# Mini-Mixer.net
KiCad netlist of a schematic drawn in EAGLE
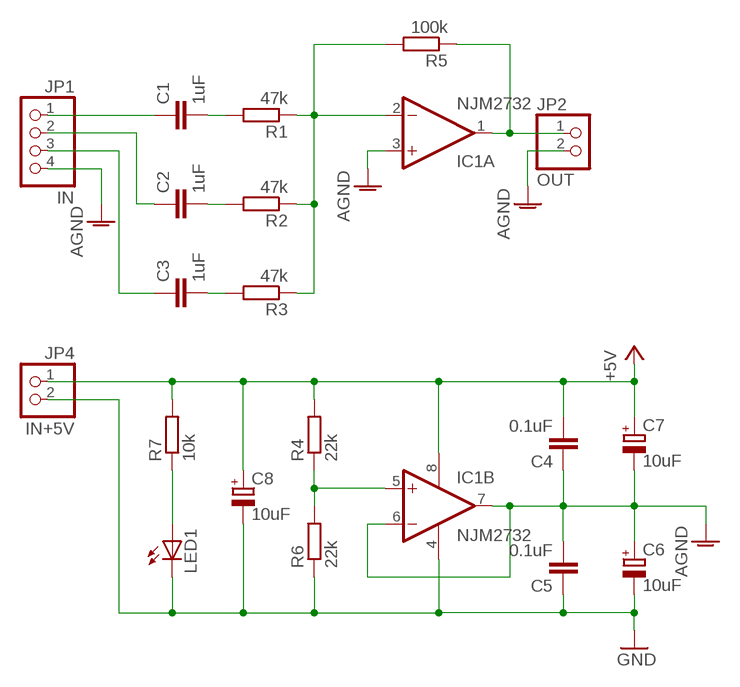
[diagram p0: schematic, sheet 1]

(export (version "E")
  (design (tool "Eeschema 10.0.6"))
  (components
    (comp (ref "C1")
      (value "1uF")
      (footprint "eagle-import:C050-050X075")
      (libsource (lib "eagle-import") (part "C-EU050-050X075"))
    )
    (comp (ref "C2")
      (value "1uF")
      (footprint "eagle-import:C050-050X075")
      (libsource (lib "eagle-import") (part "C-EU050-050X075"))
    )
    (comp (ref "C3")
      (value "1uF")
      (footprint "eagle-import:C050-050X075")
      (libsource (lib "eagle-import") (part "C-EU050-050X075"))
    )
    (comp (ref "C4")
      (value "0.1uF")
      (footprint "eagle-import:C025-024X044")
      (libsource (lib "eagle-import") (part "C-EU025-024X044"))
    )
    (comp (ref "C5")
      (value "0.1uF")
      (footprint "eagle-import:C025-024X044")
      (libsource (lib "eagle-import") (part "C-EU025-024X044"))
    )
    (comp (ref "C6")
      (value "10uF")
      (footprint "eagle-import:TT2D4L")
      (libsource (lib "eagle-import") (part "CPOL-EUTT2D4L"))
    )
    (comp (ref "C7")
      (value "10uF")
      (footprint "eagle-import:TT2D4L")
      (libsource (lib "eagle-import") (part "CPOL-EUTT2D4L"))
    )
    (comp (ref "C8")
      (value "10uF")
      (footprint "eagle-import:TT2D4L")
      (libsource (lib "eagle-import") (part "CPOL-EUTT2D4L"))
    )
    (comp (ref "IC1")
      (value "NJM2732")
      (footprint "eagle-import:DIL08")
      (libsource (lib "eagle-import") (part "4558NLM"))
    )
    (comp (ref "JP1")
      (value "IN")
      (footprint "eagle-import:1X04")
      (libsource (lib "eagle-import") (part "PINHD-1X4"))
    )
    (comp (ref "JP2")
      (value "OUT")
      (footprint "eagle-import:1X02")
      (libsource (lib "eagle-import") (part "PINHD-1X2"))
    )
    (comp (ref "JP4")
      (value "IN+5V")
      (footprint "eagle-import:1X02")
      (libsource (lib "eagle-import") (part "PINHD-1X2"))
    )
    (comp (ref "LED1")
      (value "LED3MM")
      (footprint "eagle-import:LED3MM")
      (libsource (lib "eagle-import") (part "LED3MM"))
    )
    (comp (ref "R1")
      (value "47k")
      (footprint "eagle-import:0207_7")
      (libsource (lib "eagle-import") (part "R-EU_0207/7"))
    )
    (comp (ref "R2")
      (value "47k")
      (footprint "eagle-import:0207_7")
      (libsource (lib "eagle-import") (part "R-EU_0207/7"))
    )
    (comp (ref "R3")
      (value "47k")
      (footprint "eagle-import:0207_7")
      (libsource (lib "eagle-import") (part "R-EU_0207/7"))
    )
    (comp (ref "R4")
      (value "22k")
      (footprint "eagle-import:0207_7")
      (libsource (lib "eagle-import") (part "R-EU_0207/7"))
    )
    (comp (ref "R5")
      (value "100k")
      (footprint "eagle-import:0207_7")
      (libsource (lib "eagle-import") (part "R-EU_0207/7"))
    )
    (comp (ref "R6")
      (value "22k")
      (footprint "eagle-import:0207_7")
      (libsource (lib "eagle-import") (part "R-EU_0207/7"))
    )
    (comp (ref "R7")
      (value "10k")
      (footprint "eagle-import:0207_7")
      (libsource (lib "eagle-import") (part "R-EU_0207/7"))
    )
  )
  (nets
    (net (code "1") (name "+5V") (class "Default")
      (node (ref "C4") (pin "2") (pinfunction "2_2") (pintype "passive"))
      (node (ref "C7") (pin "+") (pinfunction "+_+") (pintype "passive"))
      (node (ref "C8") (pin "+") (pinfunction "+_+") (pintype "passive"))
      (node (ref "IC1") (pin "8") (pinfunction "V+_8") (pintype "power_in"))
      (node (ref "JP4") (pin "1") (pinfunction "1_1") (pintype "passive"))
      (node (ref "R4") (pin "2") (pinfunction "2_2") (pintype "passive"))
      (node (ref "R7") (pin "2") (pinfunction "2_2") (pintype "passive"))
    )
    (net (code "2") (name "AGND") (class "Default")
      (node (ref "C4") (pin "1") (pinfunction "1_1") (pintype "passive"))
      (node (ref "C5") (pin "2") (pinfunction "2_2") (pintype "passive"))
      (node (ref "C6") (pin "+") (pinfunction "+_+") (pintype "passive"))
      (node (ref "C7") (pin "-") (pinfunction "-_-") (pintype "passive"))
      (node (ref "IC1") (pin "3") (pinfunction "+IN_3") (pintype "input"))
      (node (ref "IC1") (pin "6") (pinfunction "-IN_6") (pintype "input"))
      (node (ref "IC1") (pin "7") (pinfunction "OUT_7") (pintype "output"))
      (node (ref "JP1") (pin "4") (pinfunction "4_4") (pintype "passive"))
      (node (ref "JP2") (pin "2") (pinfunction "2_2") (pintype "passive"))
    )
    (net (code "3") (name "GND") (class "Default")
      (node (ref "C5") (pin "1") (pinfunction "1_1") (pintype "passive"))
      (node (ref "C6") (pin "-") (pinfunction "-_-") (pintype "passive"))
      (node (ref "C8") (pin "-") (pinfunction "-_-") (pintype "passive"))
      (node (ref "IC1") (pin "4") (pinfunction "V-_4") (pintype "power_in"))
      (node (ref "JP4") (pin "2") (pinfunction "2_2") (pintype "passive"))
      (node (ref "LED1") (pin "K") (pinfunction "C_K") (pintype "passive"))
      (node (ref "R6") (pin "1") (pinfunction "1_1") (pintype "passive"))
    )
    (net (code "4") (name "Net-(C1-Pad1)") (class "Default")
      (node (ref "C1") (pin "1") (pinfunction "1_1") (pintype "passive"))
      (node (ref "JP1") (pin "1") (pinfunction "1_1") (pintype "passive"))
    )
    (net (code "5") (name "Net-(C1-Pad2)") (class "Default")
      (node (ref "C1") (pin "2") (pinfunction "2_2") (pintype "passive"))
      (node (ref "R1") (pin "2") (pinfunction "2_2") (pintype "passive"))
    )
    (net (code "6") (name "Net-(C2-Pad1)") (class "Default")
      (node (ref "C2") (pin "1") (pinfunction "1_1") (pintype "passive"))
      (node (ref "JP1") (pin "2") (pinfunction "2_2") (pintype "passive"))
    )
    (net (code "7") (name "Net-(C2-Pad2)") (class "Default")
      (node (ref "C2") (pin "2") (pinfunction "2_2") (pintype "passive"))
      (node (ref "R2") (pin "2") (pinfunction "2_2") (pintype "passive"))
    )
    (net (code "8") (name "Net-(C3-Pad1)") (class "Default")
      (node (ref "C3") (pin "1") (pinfunction "1_1") (pintype "passive"))
      (node (ref "JP1") (pin "3") (pinfunction "3_3") (pintype "passive"))
    )
    (net (code "9") (name "Net-(C3-Pad2)") (class "Default")
      (node (ref "C3") (pin "2") (pinfunction "2_2") (pintype "passive"))
      (node (ref "R3") (pin "2") (pinfunction "2_2") (pintype "passive"))
    )
    (net (code "10") (name "Net-(IC1A--IN)") (class "Default")
      (node (ref "IC1") (pin "2") (pinfunction "-IN_2") (pintype "input"))
      (node (ref "R1") (pin "1") (pinfunction "1_1") (pintype "passive"))
      (node (ref "R2") (pin "1") (pinfunction "1_1") (pintype "passive"))
      (node (ref "R3") (pin "1") (pinfunction "1_1") (pintype "passive"))
      (node (ref "R5") (pin "2") (pinfunction "2_2") (pintype "passive"))
    )
    (net (code "11") (name "Net-(IC1A-OUT)") (class "Default")
      (node (ref "IC1") (pin "1") (pinfunction "OUT_1") (pintype "output"))
      (node (ref "JP2") (pin "1") (pinfunction "1_1") (pintype "passive"))
      (node (ref "R5") (pin "1") (pinfunction "1_1") (pintype "passive"))
    )
    (net (code "12") (name "Net-(IC1B-+IN)") (class "Default")
      (node (ref "IC1") (pin "5") (pinfunction "+IN_5") (pintype "input"))
      (node (ref "R4") (pin "1") (pinfunction "1_1") (pintype "passive"))
      (node (ref "R6") (pin "2") (pinfunction "2_2") (pintype "passive"))
    )
    (net (code "13") (name "Net-(LED1-PadA)") (class "Default")
      (node (ref "LED1") (pin "A") (pinfunction "A_A") (pintype "passive"))
      (node (ref "R7") (pin "1") (pinfunction "1_1") (pintype "passive"))
    )
  )
)
